# Battery.net
KiCad netlist of a schematic drawn in Altium Designer
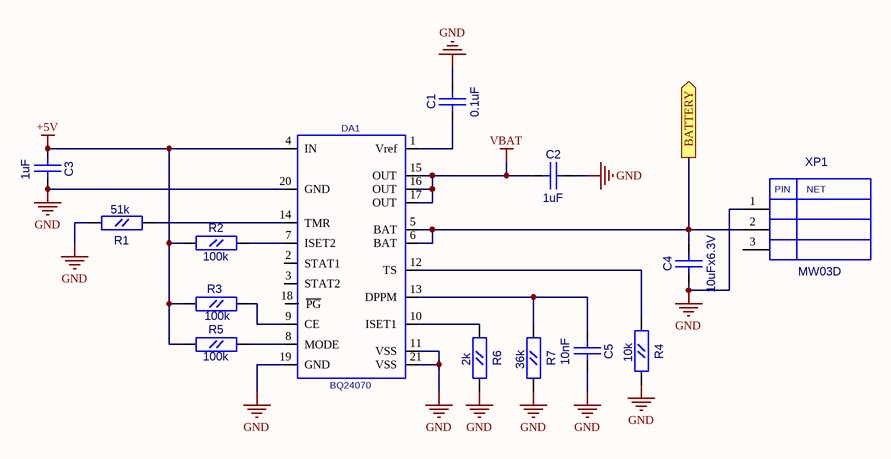
[diagram p0: Battery.SchDoc]

(export (version "E")
  (design (tool "Eeschema 10.0.6"))
  (components
    (comp (ref "C1")
      (value "0.1uF")
      (footprint "CC0603")
      (description "CC0603")
      (libsource (lib "gprs_modem_2") (part "CC0603"))
    )
    (comp (ref "C2")
      (value "1uF")
      (footprint "CC0603")
      (description "CC0603")
      (libsource (lib "gprs_modem_2") (part "CC0603"))
    )
    (comp (ref "C3")
      (value "1uF")
      (footprint "CC0603")
      (description "CC0603")
      (libsource (lib "gprs_modem_2") (part "CC0603"))
    )
    (comp (ref "C4")
      (value "10uFx6.3V")
      (footprint "CC0805")
      (description "CC0805")
      (libsource (lib "gprs_modem_2") (part "CC0805"))
    )
    (comp (ref "C5")
      (value "10nF")
      (footprint "CC0603")
      (description "CC0603")
      (libsource (lib "gprs_modem_2") (part "CC0603"))
    )
    (comp (ref "DA1")
      (value "BQ24070")
      (footprint "P-PQFP-N20")
      (libsource (lib "gprs_modem") (part "BQ24070"))
    )
    (comp (ref "R1")
      (value "51k")
      (footprint "RC0603")
      (description "RC0603")
      (libsource (lib "gprs_modem_2") (part "RC0603"))
    )
    (comp (ref "R2")
      (value "100k")
      (footprint "RC0603")
      (description "RC0603")
      (libsource (lib "gprs_modem_2") (part "RC0603"))
    )
    (comp (ref "R3")
      (value "100k")
      (footprint "RC0603")
      (description "RC0603")
      (libsource (lib "gprs_modem_2") (part "RC0603"))
    )
    (comp (ref "R4")
      (value "10k")
      (footprint "RC0603")
      (description "RC0603")
      (libsource (lib "gprs_modem_2") (part "RC0603"))
    )
    (comp (ref "R5")
      (value "100k")
      (footprint "RC0603")
      (description "RC0603")
      (libsource (lib "gprs_modem_2") (part "RC0603"))
    )
    (comp (ref "R6")
      (value "2k")
      (footprint "RC0603")
      (description "RC0603")
      (libsource (lib "gprs_modem_2") (part "RC0603"))
    )
    (comp (ref "R7")
      (value "36k")
      (footprint "RC0603")
      (description "RC0603")
      (libsource (lib "gprs_modem_2") (part "RC0603"))
    )
    (comp (ref "XP1") (value "MW03D") (footprint "MW03D") (libsource (lib "gprs_modem") (part "MW03D")))
  )
  (nets
    (net (code "1") (name "+5V") (class "Default")
      (node (ref "C3") (pin "1") (pinfunction "A_1") (pintype "passive"))
      (node (ref "DA1") (pin "4") (pinfunction "IN_4") (pintype "passive"))
      (node (ref "R2") (pin "2") (pinfunction "B_2") (pintype "passive"))
      (node (ref "R3") (pin "2") (pinfunction "B_2") (pintype "passive"))
      (node (ref "R5") (pin "2") (pinfunction "B_2") (pintype "passive"))
    )
    (net (code "2") (name "/BATTERY") (class "Default")
      (node (ref "C4") (pin "2") (pinfunction "B_2") (pintype "passive"))
      (node (ref "DA1") (pin "5") (pinfunction "BAT_5") (pintype "passive"))
      (node (ref "DA1") (pin "6") (pinfunction "BAT_6") (pintype "passive"))
      (node (ref "XP1") (pin "2") (pinfunction "2_2") (pintype "passive"))
    )
    (net (code "3") (name "GND") (class "Default")
      (node (ref "C1") (pin "2") (pinfunction "B_2") (pintype "passive"))
      (node (ref "C2") (pin "2") (pinfunction "B_2") (pintype "passive"))
      (node (ref "C3") (pin "2") (pinfunction "B_2") (pintype "passive"))
      (node (ref "C4") (pin "1") (pinfunction "A_1") (pintype "passive"))
      (node (ref "C5") (pin "2") (pinfunction "B_2") (pintype "passive"))
      (node (ref "DA1") (pin "11") (pinfunction "VSS_11") (pintype "passive"))
      (node (ref "DA1") (pin "19") (pinfunction "GND_19") (pintype "passive"))
      (node (ref "DA1") (pin "20") (pinfunction "GND_20") (pintype "passive"))
      (node (ref "DA1") (pin "21") (pinfunction "VSS_21") (pintype "passive"))
      (node (ref "R1") (pin "2") (pinfunction "B_2") (pintype "passive"))
      (node (ref "R4") (pin "2") (pinfunction "B_2") (pintype "passive"))
      (node (ref "R6") (pin "2") (pinfunction "B_2") (pintype "passive"))
      (node (ref "R7") (pin "2") (pinfunction "B_2") (pintype "passive"))
      (node (ref "XP1") (pin "1") (pinfunction "1_1") (pintype "passive"))
    )
    (net (code "4") (name "Net-(C1-A)") (class "Default")
      (node (ref "C1") (pin "1") (pinfunction "A_1") (pintype "passive"))
      (node (ref "DA1") (pin "1") (pinfunction "Vref_1") (pintype "passive"))
    )
    (net (code "5") (name "Net-(C5-A)") (class "Default")
      (node (ref "C5") (pin "1") (pinfunction "A_1") (pintype "passive"))
      (node (ref "DA1") (pin "13") (pinfunction "DPPM_13") (pintype "passive"))
      (node (ref "R7") (pin "1") (pinfunction "A_1") (pintype "passive"))
    )
    (net (code "6") (name "Net-(DA1-CE)") (class "Default")
      (node (ref "DA1") (pin "9") (pinfunction "CE_9") (pintype "passive"))
      (node (ref "R3") (pin "1") (pinfunction "A_1") (pintype "passive"))
    )
    (net (code "7") (name "Net-(DA1-ISET1)") (class "Default")
      (node (ref "DA1") (pin "10") (pinfunction "ISET1_10") (pintype "passive"))
      (node (ref "R6") (pin "1") (pinfunction "A_1") (pintype "passive"))
    )
    (net (code "8") (name "Net-(DA1-ISET2)") (class "Default")
      (node (ref "DA1") (pin "7") (pinfunction "ISET2_7") (pintype "passive"))
      (node (ref "R2") (pin "1") (pinfunction "A_1") (pintype "passive"))
    )
    (net (code "9") (name "Net-(DA1-MODE)") (class "Default")
      (node (ref "DA1") (pin "8") (pinfunction "MODE_8") (pintype "passive"))
      (node (ref "R5") (pin "1") (pinfunction "A_1") (pintype "passive"))
    )
    (net (code "10") (name "Net-(DA1-TMR)") (class "Default")
      (node (ref "DA1") (pin "14") (pinfunction "TMR_14") (pintype "passive"))
      (node (ref "R1") (pin "1") (pinfunction "A_1") (pintype "passive"))
    )
    (net (code "11") (name "Net-(DA1-TS)") (class "Default")
      (node (ref "DA1") (pin "12") (pinfunction "TS_12") (pintype "passive"))
      (node (ref "R4") (pin "1") (pinfunction "A_1") (pintype "passive"))
    )
    (net (code "12") (name "VBAT") (class "Default")
      (node (ref "C2") (pin "1") (pinfunction "A_1") (pintype "passive"))
      (node (ref "DA1") (pin "15") (pinfunction "OUT_15") (pintype "passive"))
      (node (ref "DA1") (pin "16") (pinfunction "OUT_16") (pintype "passive"))
      (node (ref "DA1") (pin "17") (pinfunction "OUT_17") (pintype "passive"))
    )
    (net (code "13") (name "unconnected-(DA1-STAT1-Pad2)") (class "Default")
      (node (ref "DA1") (pin "2") (pinfunction "STAT1_2") (pintype "passive"))
    )
    (net (code "14") (name "unconnected-(DA1-STAT2-Pad3)") (class "Default")
      (node (ref "DA1") (pin "3") (pinfunction "STAT2_3") (pintype "passive"))
    )
    (net (code "15") (name "unconnected-(DA1-~{PG}-Pad18)") (class "Default")
      (node (ref "DA1") (pin "18") (pinfunction "~{PG}_18") (pintype "passive"))
    )
    (net (code "16") (name "unconnected-(XP1-Pad3)") (class "Default")
      (node (ref "XP1") (pin "3") (pinfunction "3_3") (pintype "passive"))
    )
  )
)
